# DAC.net
KiCad netlist of a schematic drawn in Altium Designer
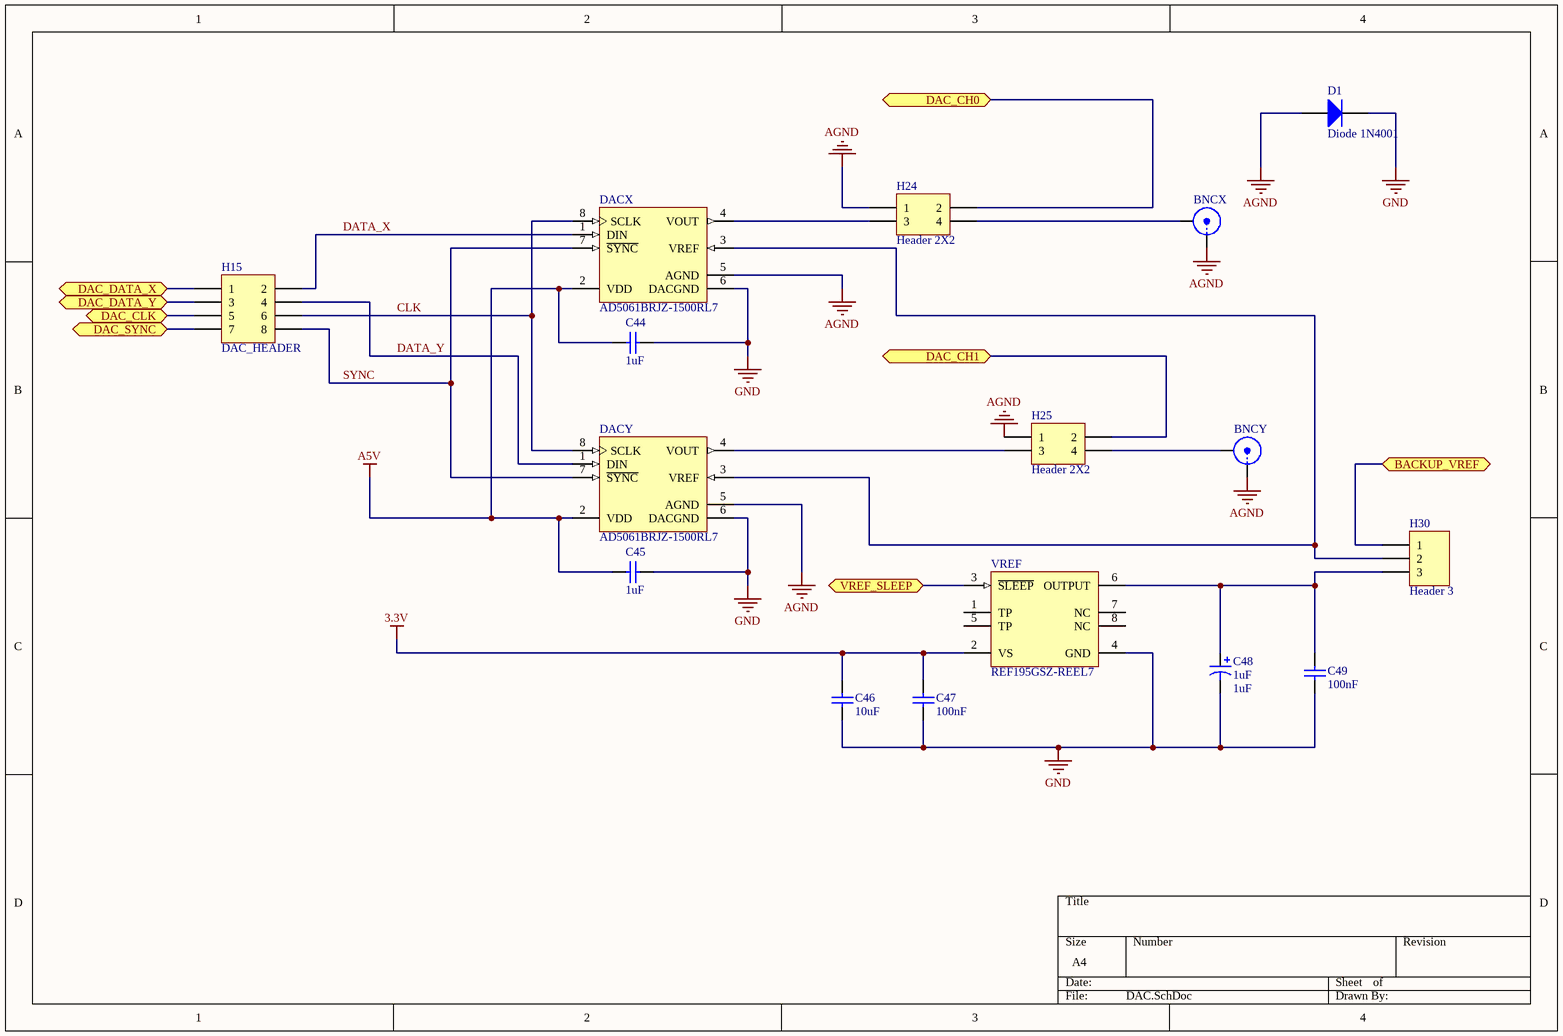
[diagram p0: DAC.SchDoc]

(export (version "E")
  (design (tool "Eeschema 10.0.6"))
  (components
    (comp (ref "BNCX")
      (value "BNC")
      (footprint "BNC_RA CON")
      (description "BNC Elbow Connector")
      (fields (field (name "PUBLISHER") "Altium Limited"))
      (libsource (lib "Miscellaneous Connectors") (part "BNC"))
    )
    (comp (ref "BNCY")
      (value "BNC")
      (footprint "BNC_RA CON")
      (description "BNC Elbow Connector")
      (fields (field (name "PUBLISHER") "Altium Limited"))
      (libsource (lib "Miscellaneous Connectors") (part "BNC"))
    )
    (comp (ref "C44")
      (value "1uF")
      (footprint "CAPC0603(1608)100_M")
      (description "CAP 0.5pF 10V Â±0.1pF 0603 (1608 Metric) Thickness 1mm SMD")
      (fields (field (name "TOLERANCE") "Â±0.1pF"))
      (libsource (lib "Altium Inc") (part "CMP-1035-00001-1"))
    )
    (comp (ref "C45")
      (value "1uF")
      (footprint "CAPC0603(1608)100_M")
      (description "CAP 0.5pF 10V Â±0.1pF 0603 (1608 Metric) Thickness 1mm SMD")
      (fields (field (name "TOLERANCE") "Â±0.1pF"))
      (libsource (lib "Altium Inc") (part "CMP-1035-00001-1"))
    )
    (comp (ref "C46")
      (value "10uF")
      (footprint "CAPC0603(1608)100_M")
      (description "CAP 0.5pF 10V Â±0.1pF 0603 (1608 Metric) Thickness 1mm SMD")
      (fields (field (name "TOLERANCE") "Â±0.1pF"))
      (libsource (lib "Altium Inc") (part "CMP-1035-00001-1"))
    )
    (comp (ref "C47")
      (value "100nF")
      (footprint "CAPC0603(1608)100_M")
      (description "CAP 0.5pF 10V Â±0.1pF 0603 (1608 Metric) Thickness 1mm SMD")
      (fields (field (name "TOLERANCE") "Â±0.1pF"))
      (libsource (lib "Altium Inc") (part "CMP-1035-00001-1"))
    )
    (comp (ref "C48")
      (value "1uF")
      (footprint "C0805")
      (description "Polarized Capacitor (Surface Mount)")
      (fields (field (name "ALTIUM_VALUE") "1uF") (field (name "PUBLISHER") "Altium Limited"))
      (libsource (lib "Miscellaneous Devices") (part "Cap Pol3"))
    )
    (comp (ref "C49")
      (value "100nF")
      (footprint "CAPC0603(1608)100_M")
      (description "CAP 0.5pF 10V Â±0.1pF 0603 (1608 Metric) Thickness 1mm SMD")
      (fields (field (name "TOLERANCE") "Â±0.1pF"))
      (libsource (lib "Altium Inc") (part "CMP-1035-00001-1"))
    )
    (comp (ref "D1")
      (value "Diode 1N4001")
      (footprint "DO-41")
      (description "1 Amp General Purpose Rectifier")
      (fields (field (name "PUBLISHER") "Altium Limited"))
      (libsource (lib "Miscellaneous Devices") (part "Diode 1N4001"))
    )
    (comp (ref "DACX")
      (value "AD5061BRJZ-1500RL7")
      (footprint "RJ-8_N")
      (fields (field (name "GENERIC PART NUMBER") "AD5061") (field (name "MANUFACTURER") "Analog Devices"))
      (libsource (lib "Analog Devices Data Converters Digital-to-Analog Converters") (part "AD5061BRJZ-1500RL7"))
    )
    (comp (ref "DACY")
      (value "AD5061BRJZ-1500RL7")
      (footprint "RJ-8_N")
      (fields (field (name "GENERIC PART NUMBER") "AD5061") (field (name "MANUFACTURER") "Analog Devices"))
      (libsource (lib "Analog Devices Data Converters Digital-to-Analog Converters") (part "AD5061BRJZ-1500RL7"))
    )
    (comp (ref "H15")
      (value "DAC_HEADER")
      (footprint "HDR2X4")
      (description "Header, 4-Pin, Dual row")
      (fields (field (name "PUBLISHER") "Altium Limited"))
      (libsource (lib "Miscellaneous Connectors") (part "Header 4X2"))
    )
    (comp (ref "H24")
      (value "Header 2X2")
      (footprint "HDR2X2")
      (description "Header, 2-Pin, Dual row")
      (fields (field (name "PUBLISHER") "Altium Limited"))
      (libsource (lib "Miscellaneous Connectors") (part "Header 2X2"))
    )
    (comp (ref "H25")
      (value "Header 2X2")
      (footprint "HDR2X2")
      (description "Header, 2-Pin, Dual row")
      (fields (field (name "PUBLISHER") "Altium Limited"))
      (libsource (lib "Miscellaneous Connectors") (part "Header 2X2"))
    )
    (comp (ref "H30")
      (value "Header 3")
      (footprint "HDR1X3")
      (description "Header, 3-Pin")
      (fields (field (name "PUBLISHER") "Altium Limited"))
      (libsource (lib "Miscellaneous Connectors") (part "Header 3"))
    )
    (comp (ref "VREF")
      (value "REF195GSZ-REEL7")
      (footprint "ADI-R-8_N")
      (fields (field (name "MANUFACTURER") "Analog Devices"))
      (libsource (lib "Analog Devices Amplifiers and Linear Voltage References") (part "REF195GSZ-REEL7"))
    )
  )
  (nets
    (net (code "1") (name "/BACKUP_VREF") (class "Default")
      (node (ref "H30") (pin "1") (pinfunction "1_1") (pintype "passive"))
    )
    (net (code "2") (name "/CLK") (class "Default")
      (node (ref "DACX") (pin "8") (pinfunction "SCLK_8") (pintype "input"))
      (node (ref "DACY") (pin "8") (pinfunction "SCLK_8") (pintype "input"))
      (node (ref "H15") (pin "6") (pinfunction "6_6") (pintype "passive"))
    )
    (net (code "3") (name "/DAC_CH0") (class "Default")
      (node (ref "H24") (pin "2") (pinfunction "2_2") (pintype "passive"))
    )
    (net (code "4") (name "/DAC_CH1") (class "Default")
      (node (ref "H25") (pin "2") (pinfunction "2_2") (pintype "passive"))
    )
    (net (code "5") (name "/DAC_CLK") (class "Default")
      (node (ref "H15") (pin "5") (pinfunction "5_5") (pintype "passive"))
    )
    (net (code "6") (name "/DAC_DATA_X") (class "Default")
      (node (ref "H15") (pin "1") (pinfunction "1_1") (pintype "passive"))
    )
    (net (code "7") (name "/DAC_DATA_Y") (class "Default")
      (node (ref "H15") (pin "3") (pinfunction "3_3") (pintype "passive"))
    )
    (net (code "8") (name "/DAC_SYNC") (class "Default")
      (node (ref "H15") (pin "7") (pinfunction "7_7") (pintype "passive"))
    )
    (net (code "9") (name "/DATA_X") (class "Default")
      (node (ref "DACX") (pin "1") (pinfunction "DIN_1") (pintype "input"))
      (node (ref "H15") (pin "2") (pinfunction "2_2") (pintype "passive"))
    )
    (net (code "10") (name "/DATA_Y") (class "Default")
      (node (ref "DACY") (pin "1") (pinfunction "DIN_1") (pintype "input"))
      (node (ref "H15") (pin "4") (pinfunction "4_4") (pintype "passive"))
    )
    (net (code "11") (name "/SYNC") (class "Default")
      (node (ref "DACX") (pin "7") (pinfunction "~{SYNC}_7") (pintype "input"))
      (node (ref "DACY") (pin "7") (pinfunction "~{SYNC}_7") (pintype "input"))
      (node (ref "H15") (pin "8") (pinfunction "8_8") (pintype "passive"))
    )
    (net (code "12") (name "/VREF_SLEEP") (class "Default")
      (node (ref "VREF") (pin "3") (pinfunction "~{SLEEP}_3") (pintype "input"))
    )
    (net (code "13") (name "3.3V") (class "Default")
      (node (ref "C46") (pin "2") (pinfunction "2_2") (pintype "passive"))
      (node (ref "C47") (pin "2") (pinfunction "2_2") (pintype "passive"))
      (node (ref "VREF") (pin "2") (pinfunction "VS_2") (pintype "power_in"))
    )
    (net (code "14") (name "A5V") (class "Default")
      (node (ref "C44") (pin "1") (pinfunction "1_1") (pintype "passive"))
      (node (ref "C45") (pin "1") (pinfunction "1_1") (pintype "passive"))
      (node (ref "DACX") (pin "2") (pinfunction "VDD_2") (pintype "power_in"))
      (node (ref "DACY") (pin "2") (pinfunction "VDD_2") (pintype "power_in"))
    )
    (net (code "15") (name "AGND") (class "Default")
      (node (ref "BNCX") (pin "1") (pinfunction "X_1") (pintype "passive"))
      (node (ref "BNCY") (pin "1") (pinfunction "X_1") (pintype "passive"))
      (node (ref "D1") (pin "1") (pinfunction "A_1") (pintype "passive"))
      (node (ref "DACX") (pin "5") (pinfunction "AGND_5") (pintype "power_in"))
      (node (ref "DACY") (pin "5") (pinfunction "AGND_5") (pintype "power_in"))
      (node (ref "H24") (pin "1") (pinfunction "1_1") (pintype "passive"))
      (node (ref "H25") (pin "1") (pinfunction "1_1") (pintype "passive"))
    )
    (net (code "16") (name "GND") (class "Default")
      (node (ref "C44") (pin "2") (pinfunction "2_2") (pintype "passive"))
      (node (ref "C45") (pin "2") (pinfunction "2_2") (pintype "passive"))
      (node (ref "C46") (pin "1") (pinfunction "1_1") (pintype "passive"))
      (node (ref "C47") (pin "1") (pinfunction "1_1") (pintype "passive"))
      (node (ref "C48") (pin "2") (pinfunction "2_2") (pintype "passive"))
      (node (ref "C49") (pin "1") (pinfunction "1_1") (pintype "passive"))
      (node (ref "D1") (pin "2") (pinfunction "K_2") (pintype "passive"))
      (node (ref "DACX") (pin "6") (pinfunction "DACGND_6") (pintype "power_in"))
      (node (ref "DACY") (pin "6") (pinfunction "DACGND_6") (pintype "power_in"))
      (node (ref "VREF") (pin "4") (pinfunction "GND_4") (pintype "power_in"))
    )
    (net (code "17") (name "Net-(BNCX-Y)") (class "Default")
      (node (ref "BNCX") (pin "2") (pinfunction "Y_2") (pintype "passive"))
      (node (ref "H24") (pin "4") (pinfunction "4_4") (pintype "passive"))
    )
    (net (code "18") (name "Net-(BNCY-Y)") (class "Default")
      (node (ref "BNCY") (pin "2") (pinfunction "Y_2") (pintype "passive"))
      (node (ref "H25") (pin "4") (pinfunction "4_4") (pintype "passive"))
    )
    (net (code "19") (name "Net-(DACX-VOUT)") (class "Default")
      (node (ref "DACX") (pin "4") (pinfunction "VOUT_4") (pintype "output"))
      (node (ref "H24") (pin "3") (pinfunction "3_3") (pintype "passive"))
    )
    (net (code "20") (name "Net-(DACX-VREF)") (class "Default")
      (node (ref "DACX") (pin "3") (pinfunction "VREF_3") (pintype "input"))
      (node (ref "DACY") (pin "3") (pinfunction "VREF_3") (pintype "input"))
      (node (ref "H30") (pin "2") (pinfunction "2_2") (pintype "passive"))
    )
    (net (code "21") (name "Net-(DACY-VOUT)") (class "Default")
      (node (ref "DACY") (pin "4") (pinfunction "VOUT_4") (pintype "output"))
      (node (ref "H25") (pin "3") (pinfunction "3_3") (pintype "passive"))
    )
    (net (code "22") (name "Net-(VREF-OUTPUT)") (class "Default")
      (node (ref "C48") (pin "1") (pinfunction "1_1") (pintype "passive"))
      (node (ref "C49") (pin "2") (pinfunction "2_2") (pintype "passive"))
      (node (ref "H30") (pin "3") (pinfunction "3_3") (pintype "passive"))
      (node (ref "VREF") (pin "6") (pinfunction "OUTPUT_6") (pintype "tri_state"))
    )
    (net (code "23") (name "unconnected-(VREF-NC-Pad7)") (class "Default")
      (node (ref "VREF") (pin "7") (pinfunction "NC_7") (pintype "passive"))
    )
    (net (code "24") (name "unconnected-(VREF-NC-Pad8)") (class "Default")
      (node (ref "VREF") (pin "8") (pinfunction "NC_8") (pintype "passive"))
    )
    (net (code "25") (name "unconnected-(VREF-TP-Pad1)") (class "Default")
      (node (ref "VREF") (pin "1") (pinfunction "TP_1") (pintype "passive"))
    )
    (net (code "26") (name "unconnected-(VREF-TP-Pad5)") (class "Default")
      (node (ref "VREF") (pin "5") (pinfunction "TP_5") (pintype "passive"))
    )
  )
)
